# quad_spi_flash.net
KiCad netlist of a schematic drawn in Altium Designer
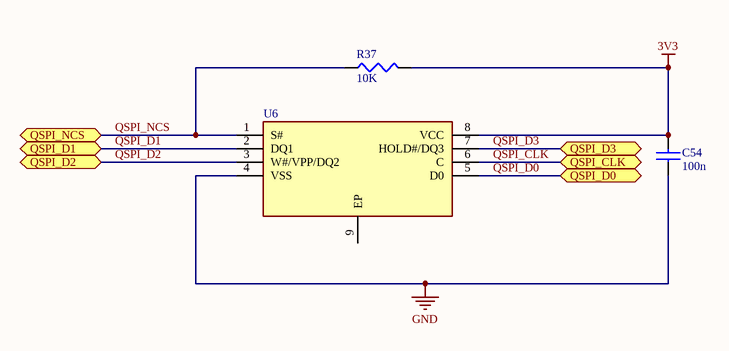
[diagram p0: quad_spi_flash.SchDoc]

(export (version "E")
  (design (tool "Eeschema 10.0.6"))
  (components
    (comp (ref "C54")
      (value "100n")
      (footprint "C0402")
      (description "CAP CER .10UF 50V X5R 10% 0402")
      (fields
        (field (name "MANUFACTURER") "TDK Corporation")
        (field (name "MANUFACTURER PART NUMBER") "C1005X5R1H104K")
      )
      (libsource (lib "iMX6_Rex_Development_Baseboard_V1I1") (part "C1005X5R1H104K"))
    )
    (comp (ref "R37")
      (value "10K")
      (footprint "R0402")
      (description "RES 10.0K OHM 1/16W 1% 0402 SMD")
      (fields
        (field (name "MANUFACTURER") "Yageo")
        (field (name "MANUFACTURER PART NUMBER") "RC0402FR-0710KL")
      )
      (libsource (lib "iMX6_Rex_Development_Baseboard_V1I1") (part "RC0402FR-0710KL"))
    )
    (comp (ref "U6")
      (value "N25Q128A13EF840E")
      (footprint "SamacSys:SON127P800X600X100-9N-D")
      (description "Integrated Circuit")
      (fields (field (name "MOUSER PART NUMBER") "340-182262"))
      (libsource (lib "*") (part "N25Q128A13EF840E"))
    )
  )
  (nets
    (net (code "1") (name "/QSPI_CLK") (class "Default")
      (node (ref "U6") (pin "6") (pinfunction "C_6") (pintype "passive"))
    )
    (net (code "2") (name "/QSPI_D0") (class "Default")
      (node (ref "U6") (pin "5") (pinfunction "D0_5") (pintype "passive"))
    )
    (net (code "3") (name "/QSPI_D1") (class "Default")
      (node (ref "U6") (pin "2") (pinfunction "DQ1_2") (pintype "passive"))
    )
    (net (code "4") (name "/QSPI_D2") (class "Default")
      (node (ref "U6") (pin "3") (pinfunction "W#/VPP/DQ2_3") (pintype "passive"))
    )
    (net (code "5") (name "/QSPI_D3") (class "Default")
      (node (ref "U6") (pin "7") (pinfunction "HOLD#/DQ3_7") (pintype "passive"))
    )
    (net (code "6") (name "/QSPI_NCS") (class "Default")
      (node (ref "R37") (pin "1") (pinfunction "1_1") (pintype "passive"))
      (node (ref "U6") (pin "1") (pinfunction "S#_1") (pintype "passive"))
    )
    (net (code "7") (name "3V3") (class "Default")
      (node (ref "C54") (pin "2") (pinfunction "2_2") (pintype "passive"))
      (node (ref "R37") (pin "2") (pinfunction "2_2") (pintype "passive"))
      (node (ref "U6") (pin "8") (pinfunction "VCC_8") (pintype "passive"))
    )
    (net (code "8") (name "GND") (class "Default")
      (node (ref "C54") (pin "1") (pinfunction "1_1") (pintype "passive"))
      (node (ref "U6") (pin "4") (pinfunction "VSS_4") (pintype "passive"))
    )
    (net (code "9") (name "unconnected-(U6-EP-Pad9)") (class "Default")
      (node (ref "U6") (pin "9") (pinfunction "EP_9") (pintype "passive"))
    )
  )
)
